# 02-Power_5v0.net
KiCad netlist of a schematic drawn in Altium Designer
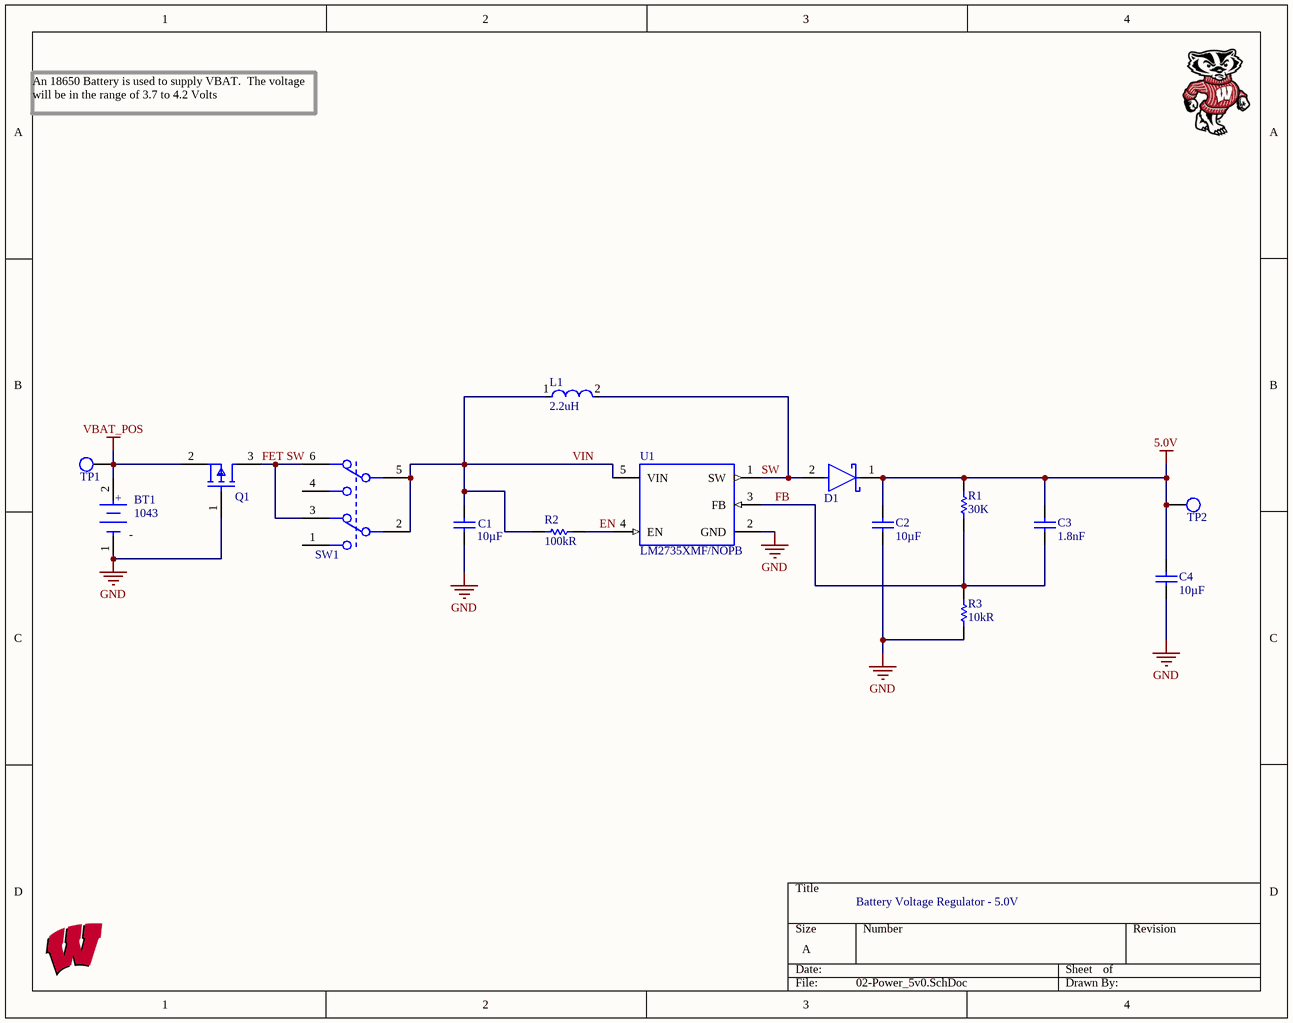
[diagram p0: 02-Power_5v0.SchDoc]

(export (version "E")
  (design (tool "Eeschema 10.0.6"))
  (components
    (comp (ref "BT1")
      (value "1043")
      (footprint "Keystone_1043_0")
      (description "Cylindrical Battery Contacts, Clips, Holders & Springs 18650 PCB PLASTIC BATT HLDR THM 1 CELL")
      (fields (field (name "MANUFACTURER PART NUMBER 1") "1043"))
      (libsource (lib "Battery") (part "1043"))
    )
    (comp (ref "C1")
      (value "10µF")
      (footprint "CAP_0805")
      (description "CAP CER 10UF 10V X5R 0805")
      (fields
        (field (name "MANUFACTURER") "Samsung Electro-Mechanics America, Inc.")
        (field (name "MANUFACTURER PART NUMBER") "CL21A106KPCLQNC")
      )
      (libsource (lib "Cap_Ceramic") (part "CAP_0805_U_010_00"))
    )
    (comp (ref "C2")
      (value "10µF")
      (footprint "CAP_0805")
      (description "CAP CER 10UF 10V X5R 0805")
      (fields
        (field (name "MANUFACTURER") "Samsung Electro-Mechanics America, Inc.")
        (field (name "MANUFACTURER PART NUMBER") "CL21A106KPCLQNC")
      )
      (libsource (lib "Cap_Ceramic") (part "CAP_0805_U_010_00"))
    )
    (comp (ref "C3")
      (value "CAP_0805_N_001_80")
      (footprint "CAP_0805")
      (fields
        (field (name "TOLERANCE") "5%")
        (field (name "VOLTAGE") "50V")
        (field (name "CAPACITANCE") "1.8nF")
      )
      (libsource (lib "Cap_Ceramic") (part "CAP_0805_N_001_80"))
    )
    (comp (ref "C4")
      (value "10µF")
      (footprint "CAP_0805")
      (description "CAP CER 10UF 10V X5R 0805")
      (fields
        (field (name "MANUFACTURER") "Samsung Electro-Mechanics America, Inc.")
        (field (name "MANUFACTURER PART NUMBER") "CL21A106KPCLQNC")
      )
      (libsource (lib "Cap_Ceramic") (part "CAP_0805_U_010_00"))
    )
    (comp (ref "D1")
      (value "SM5817PL-TP")
      (footprint "On_Semiconductor_425-04_IPC_A")
      (description "DIODE SCHOTTKY 20V 1A SOD123FL")
      (libsource (lib "Diodes") (part "SM5817PL-TP"))
    )
    (comp (ref "L1")
      (value "NRS4018T2R2MDGJ")
      (footprint "IND_TAIYO_NRS4018_TAY")
      (description "Inductor Power Shielded Wirewound 2.2uH 20% 100KHz Ferrite 2.2A 0.0504Ohm DCR 1515 T/R")
      (fields (field (name "TOLERANCE") "20%") (field (name "INDUCTANCE") "2.2uH"))
      (libsource (lib "Inductors") (part "NRS4018T2R2MDGJ"))
    )
    (comp (ref "Q1")
      (value "SSM3J328R,LF")
      (footprint "SOT-23_M")
      (description "MOSFET P-CH 20V 6A SOT23F")
      (libsource (lib "Transistors") (part "SSM3J328R,LF"))
    )
    (comp (ref "R1")
      (value "30K")
      (footprint "RES_0805")
      (description "Res Thick Film 0805 30K Ohm 1% 0.125W(1/8W) ±100ppm/°C Pad SMD Automotive T/R")
      (fields (field (name "TOLERANCE") "1%") (field (name "RESISTANCE") "30K"))
      (libsource (lib "Resistors") (part "RES_0805_K_030.00"))
    )
    (comp (ref "R2")
      (value "RES_0805_K_010.00")
      (footprint "RES_0805")
      (description "RES SMD 10K OHM 1% 1/8W 0805")
      (fields (field (name "TOLERANCE") "1%") (field (name "RESISTANCE") "100kR"))
      (libsource (lib "Resistors") (part "RES_0805_K_010.00"))
    )
    (comp (ref "R3")
      (value "RES_0805_K_010.00")
      (footprint "RES_0805")
      (description "RES SMD 10K OHM 1% 1/8W 0805")
      (fields (field (name "TOLERANCE") "1%") (field (name "RESISTANCE") "10kR"))
      (libsource (lib "Resistors") (part "RES_0805_K_010.00"))
    )
    (comp (ref "SW1")
      (value "JS202011SCQN")
      (footprint "C&K_Components_0_MFG")
      (description "C & K COMPONENTS - JS202011SCQN - SWITCH, DPDT, 0.6A, 6VDC, SMD")
      (libsource (lib "Switches") (part "JS202011SCQN"))
    )
    (comp (ref "TP1")
      (value "TP_1206")
      (footprint "TP-SMC-1206")
      (description "Test Point SMD 1206")
      (fields
        (field (name "MANUFACTURER") "TE Connectivity (Tyco Electronics)")
        (field (name "MANUFACTURER PART NUMBER") "1625854-1")
      )
      (libsource (lib "Mechanical") (part "TP_1206"))
    )
    (comp (ref "TP2")
      (value "TP_1206")
      (footprint "TP-SMC-1206")
      (description "Test Point SMD 1206")
      (fields
        (field (name "MANUFACTURER") "TE Connectivity (Tyco Electronics)")
        (field (name "MANUFACTURER PART NUMBER") "1625854-1")
      )
      (libsource (lib "Mechanical") (part "TP_1206"))
    )
    (comp (ref "U1")
      (value "LM2735XMF-NOPB")
      (footprint "Texas_Instruments_DBV0005A_0")
      (description "IC REG MULT CONFG ADJ 2.1A SOT23")
      (fields (field (name "MANUFACTURER PART NUMBER 1") "LM2735XMF/NOPB"))
      (libsource (lib "Regulators") (part "LM2735XMF-NOPB"))
    )
  )
  (nets
    (net (code "1") (name "/EN") (class "Default")
      (node (ref "R2") (pin "1") (pinfunction "1_1") (pintype "passive"))
      (node (ref "U1") (pin "4") (pinfunction "EN_4") (pintype "input"))
    )
    (net (code "2") (name "/FB") (class "Default")
      (node (ref "C3") (pin "1") (pinfunction "1_1") (pintype "passive"))
      (node (ref "R1") (pin "2") (pinfunction "2_2") (pintype "passive"))
      (node (ref "R3") (pin "2") (pinfunction "2_2") (pintype "passive"))
      (node (ref "U1") (pin "3") (pinfunction "FB_3") (pintype "input"))
    )
    (net (code "3") (name "/FET SW") (class "Default")
      (node (ref "Q1") (pin "3") (pinfunction "Drain_3") (pintype "passive"))
      (node (ref "SW1") (pin "3") (pinfunction "3_3") (pintype "passive"))
      (node (ref "SW1") (pin "6") (pinfunction "6_6") (pintype "passive"))
    )
    (net (code "4") (name "/SW") (class "Default")
      (node (ref "D1") (pin "2") (pinfunction "A_2") (pintype "passive"))
      (node (ref "L1") (pin "2") (pinfunction "2_2") (pintype "passive"))
      (node (ref "U1") (pin "1") (pinfunction "SW_1") (pintype "output"))
    )
    (net (code "5") (name "/VIN") (class "Default")
      (node (ref "C1") (pin "2") (pinfunction "2_2") (pintype "passive"))
      (node (ref "L1") (pin "1") (pinfunction "1_1") (pintype "passive"))
      (node (ref "R2") (pin "2") (pinfunction "2_2") (pintype "passive"))
      (node (ref "SW1") (pin "2") (pinfunction "2_2") (pintype "passive"))
      (node (ref "SW1") (pin "5") (pinfunction "5_5") (pintype "passive"))
      (node (ref "U1") (pin "5") (pinfunction "VIN_5") (pintype "power_in"))
    )
    (net (code "6") (name "5.0V") (class "Default")
      (node (ref "C2") (pin "2") (pinfunction "2_2") (pintype "passive"))
      (node (ref "C3") (pin "2") (pinfunction "2_2") (pintype "passive"))
      (node (ref "C4") (pin "2") (pinfunction "2_2") (pintype "passive"))
      (node (ref "D1") (pin "1") (pinfunction "C_1") (pintype "passive"))
      (node (ref "R1") (pin "1") (pinfunction "1_1") (pintype "passive"))
      (node (ref "TP2") (pin "1") (pintype "passive"))
    )
    (net (code "7") (name "GND") (class "Default")
      (node (ref "BT1") (pin "1") (pinfunction "C_1") (pintype "passive"))
      (node (ref "C1") (pin "1") (pinfunction "1_1") (pintype "passive"))
      (node (ref "C2") (pin "1") (pinfunction "1_1") (pintype "passive"))
      (node (ref "C4") (pin "1") (pinfunction "1_1") (pintype "passive"))
      (node (ref "Q1") (pin "1") (pinfunction "Gate_1") (pintype "passive"))
      (node (ref "R3") (pin "1") (pinfunction "1_1") (pintype "passive"))
      (node (ref "U1") (pin "2") (pinfunction "GND_2") (pintype "power_in"))
    )
    (net (code "8") (name "VBAT_POS") (class "Default")
      (node (ref "BT1") (pin "2") (pinfunction "A_2") (pintype "passive"))
      (node (ref "Q1") (pin "2") (pinfunction "Source_2") (pintype "passive"))
      (node (ref "TP1") (pin "1") (pintype "passive"))
    )
    (net (code "9") (name "unconnected-(SW1-Pad1)") (class "Default")
      (node (ref "SW1") (pin "1") (pinfunction "1_1") (pintype "passive"))
    )
    (net (code "10") (name "unconnected-(SW1-Pad4)") (class "Default")
      (node (ref "SW1") (pin "4") (pinfunction "4_4") (pintype "passive"))
    )
  )
)
